# Monlock5x7_buffered.net
KiCad netlist of a schematic drawn in EAGLE
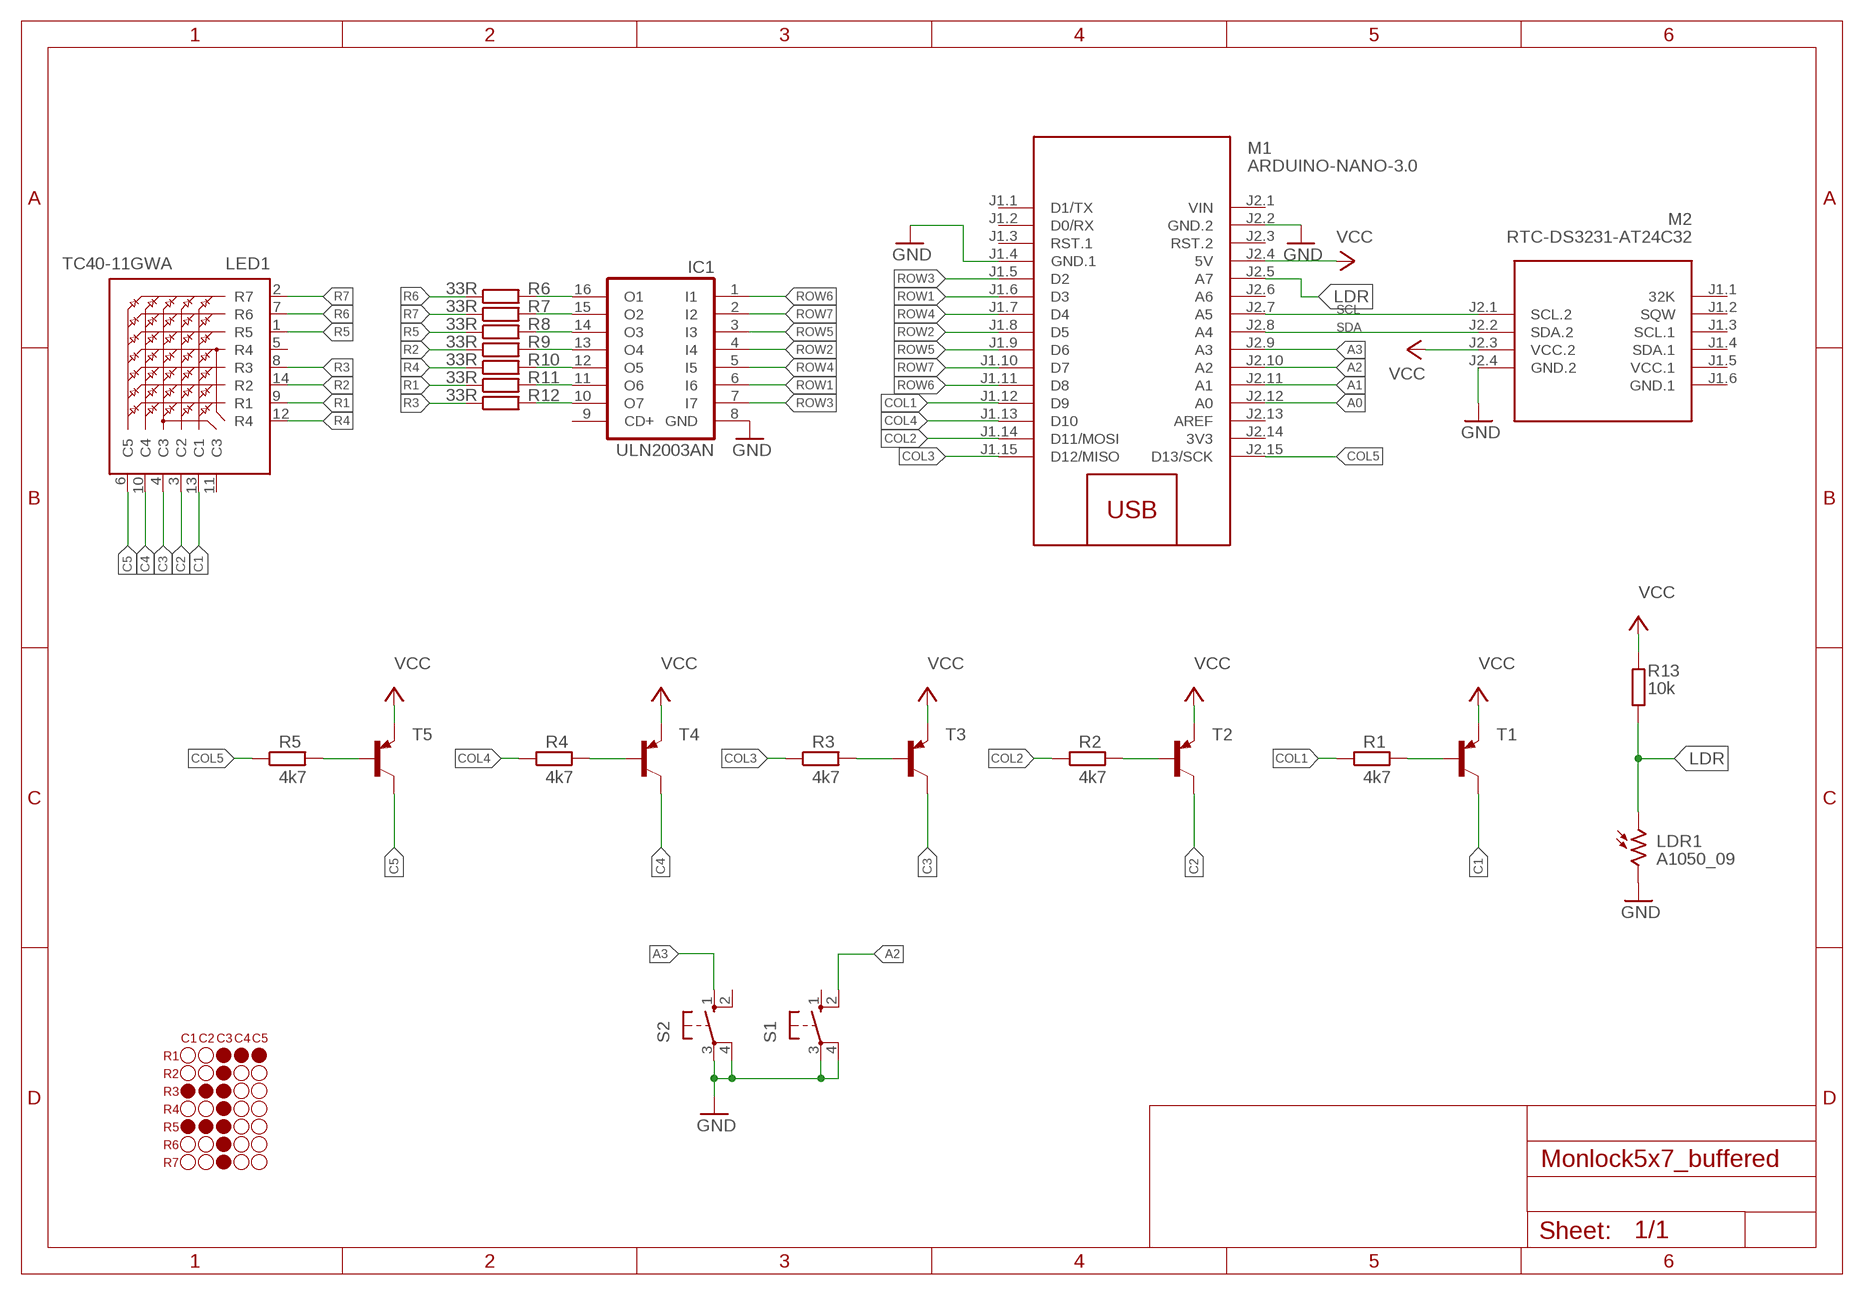
[diagram p0: schematic, sheet 1]

(export (version "E")
  (design (tool "Eeschema 10.0.6"))
  (components
    (comp (ref "IC1")
      (value "ULN2003AN")
      (footprint "eagle-import:DIL16")
      (libsource (lib "eagle-import") (part "ULN2003AN"))
    )
    (comp (ref "LDR1")
      (value "A1050_09")
      (footprint "eagle-import:T0-46-A10XX")
      (libsource (lib "eagle-import") (part "A1050_09"))
    )
    (comp (ref "LED1")
      (value "TC40-11GWA")
      (footprint "eagle-import:TC40-11GWA")
      (libsource (lib "eagle-import") (part "TC40-11GWA"))
    )
    (comp (ref "M1")
      (value "ARDUINO-NANO-3.0")
      (footprint "eagle-import:ARDUINO-NANO-3.0")
      (libsource (lib "eagle-import") (part "ARDUINO-NANO-3.0"))
    )
    (comp (ref "M2")
      (value "RTC-DS3231-AT24C32")
      (footprint "eagle-import:RTC-DS3231-AT24C32")
      (libsource (lib "eagle-import") (part "RTC-DS3231-AT24C32"))
    )
    (comp (ref "R1")
      (value "4k7")
      (footprint "eagle-import:0204_7")
      (libsource (lib "eagle-import") (part "R-EU_0204/7"))
    )
    (comp (ref "R2")
      (value "4k7")
      (footprint "eagle-import:0204_7")
      (libsource (lib "eagle-import") (part "R-EU_0204/7"))
    )
    (comp (ref "R3")
      (value "4k7")
      (footprint "eagle-import:0204_7")
      (libsource (lib "eagle-import") (part "R-EU_0204/7"))
    )
    (comp (ref "R4")
      (value "4k7")
      (footprint "eagle-import:0204_7")
      (libsource (lib "eagle-import") (part "R-EU_0204/7"))
    )
    (comp (ref "R5")
      (value "4k7")
      (footprint "eagle-import:0204_7")
      (libsource (lib "eagle-import") (part "R-EU_0204/7"))
    )
    (comp (ref "R6")
      (value "33R")
      (footprint "eagle-import:0204_7")
      (libsource (lib "eagle-import") (part "R-EU_0204/7"))
    )
    (comp (ref "R7")
      (value "33R")
      (footprint "eagle-import:0204_7")
      (libsource (lib "eagle-import") (part "R-EU_0204/7"))
    )
    (comp (ref "R8")
      (value "33R")
      (footprint "eagle-import:0204_7")
      (libsource (lib "eagle-import") (part "R-EU_0204/7"))
    )
    (comp (ref "R9")
      (value "33R")
      (footprint "eagle-import:0204_7")
      (libsource (lib "eagle-import") (part "R-EU_0204/7"))
    )
    (comp (ref "R10")
      (value "33R")
      (footprint "eagle-import:0204_7")
      (libsource (lib "eagle-import") (part "R-EU_0204/7"))
    )
    (comp (ref "R11")
      (value "33R")
      (footprint "eagle-import:0204_7")
      (libsource (lib "eagle-import") (part "R-EU_0204/7"))
    )
    (comp (ref "R12")
      (value "33R")
      (footprint "eagle-import:0204_7")
      (libsource (lib "eagle-import") (part "R-EU_0204/7"))
    )
    (comp (ref "R13")
      (value "10k")
      (footprint "eagle-import:0204_7")
      (libsource (lib "eagle-import") (part "R-EU_0204/7"))
    )
    (comp (ref "S1")
      (value "40-XX")
      (footprint "eagle-import:B3F-40XX")
      (fields (field (name "MF") "OMRON COMPONENTS USA") (field (name "MPN") "B3F-4000"))
      (libsource (lib "eagle-import") (part "40-XX"))
    )
    (comp (ref "S2")
      (value "40-XX")
      (footprint "eagle-import:B3F-40XX")
      (fields (field (name "MF") "OMRON COMPONENTS USA") (field (name "MPN") "B3F-4000"))
      (libsource (lib "eagle-import") (part "40-XX"))
    )
    (comp (ref "T1")
      (value "BC327-PNP-TO92-EBC")
      (footprint "eagle-import:TO92-EBC")
      (libsource (lib "eagle-import") (part "-PNP-TO92-EBCBC327"))
    )
    (comp (ref "T2")
      (value "BC327-PNP-TO92-EBC")
      (footprint "eagle-import:TO92-EBC")
      (libsource (lib "eagle-import") (part "-PNP-TO92-EBCBC327"))
    )
    (comp (ref "T3")
      (value "BC327-PNP-TO92-EBC")
      (footprint "eagle-import:TO92-EBC")
      (libsource (lib "eagle-import") (part "-PNP-TO92-EBCBC327"))
    )
    (comp (ref "T4")
      (value "BC327-PNP-TO92-EBC")
      (footprint "eagle-import:TO92-EBC")
      (libsource (lib "eagle-import") (part "-PNP-TO92-EBCBC327"))
    )
    (comp (ref "T5")
      (value "BC327-PNP-TO92-EBC")
      (footprint "eagle-import:TO92-EBC")
      (libsource (lib "eagle-import") (part "-PNP-TO92-EBCBC327"))
    )
  )
  (nets
    (net (code "1") (name "/3V3") (class "Default")
      (node (ref "M1") (pin "J2.14") (pinfunction "3V3_J2.14") (pintype "power_in"))
    )
    (net (code "2") (name "/GND.1") (class "Default")
      (node (ref "M2") (pin "J1.6") (pinfunction "GND.1_J1.6") (pintype "power_in"))
    )
    (net (code "3") (name "/SCL") (class "Default")
      (node (ref "M1") (pin "J2.7") (pinfunction "A5_J2.7") (pintype "bidirectional"))
      (node (ref "M2") (pin "J2.1") (pinfunction "SCL.2_J2.1") (pintype "bidirectional"))
    )
    (net (code "4") (name "/SDA") (class "Default")
      (node (ref "M1") (pin "J2.8") (pinfunction "A4_J2.8") (pintype "bidirectional"))
      (node (ref "M2") (pin "J2.2") (pinfunction "SDA.2_J2.2") (pintype "bidirectional"))
    )
    (net (code "5") (name "/VCC.1") (class "Default")
      (node (ref "M2") (pin "J1.5") (pinfunction "VCC.1_J1.5") (pintype "power_in"))
    )
    (net (code "6") (name "/VIN") (class "Default")
      (node (ref "M1") (pin "J2.1") (pinfunction "VIN_J2.1") (pintype "power_in"))
    )
    (net (code "7") (name "A0") (class "Default")
      (node (ref "M1") (pin "J2.12") (pinfunction "A0_J2.12") (pintype "bidirectional"))
    )
    (net (code "8") (name "A1") (class "Default")
      (node (ref "M1") (pin "J2.11") (pinfunction "A1_J2.11") (pintype "bidirectional"))
    )
    (net (code "9") (name "A2") (class "Default")
      (node (ref "M1") (pin "J2.10") (pinfunction "A2_J2.10") (pintype "bidirectional"))
      (node (ref "S1") (pin "2") (pinfunction "S1_2") (pintype "passive"))
    )
    (net (code "10") (name "A3") (class "Default")
      (node (ref "M1") (pin "J2.9") (pinfunction "A3_J2.9") (pintype "bidirectional"))
      (node (ref "S2") (pin "1") (pinfunction "S_1") (pintype "passive"))
    )
    (net (code "11") (name "C1") (class "Default")
      (node (ref "LED1") (pin "13") (pinfunction "C1_13") (pintype "passive"))
      (node (ref "T1") (pin "C") (pinfunction "C_C") (pintype "passive"))
    )
    (net (code "12") (name "C2") (class "Default")
      (node (ref "LED1") (pin "3") (pinfunction "C2_3") (pintype "passive"))
      (node (ref "T2") (pin "C") (pinfunction "C_C") (pintype "passive"))
    )
    (net (code "13") (name "C3") (class "Default")
      (node (ref "LED1") (pin "4") (pinfunction "C3_4") (pintype "passive"))
      (node (ref "T3") (pin "C") (pinfunction "C_C") (pintype "passive"))
    )
    (net (code "14") (name "C4") (class "Default")
      (node (ref "LED1") (pin "10") (pinfunction "C4_10") (pintype "passive"))
      (node (ref "T4") (pin "C") (pinfunction "C_C") (pintype "passive"))
    )
    (net (code "15") (name "C5") (class "Default")
      (node (ref "LED1") (pin "6") (pinfunction "C5_6") (pintype "passive"))
      (node (ref "T5") (pin "C") (pinfunction "C_C") (pintype "passive"))
    )
    (net (code "16") (name "COL1") (class "Default")
      (node (ref "M1") (pin "J1.12") (pinfunction "D9_J1.12") (pintype "bidirectional"))
      (node (ref "R1") (pin "1") (pinfunction "1_1") (pintype "passive"))
    )
    (net (code "17") (name "COL2") (class "Default")
      (node (ref "M1") (pin "J1.14") (pinfunction "D11/MOSI_J1.14") (pintype "bidirectional"))
      (node (ref "R2") (pin "1") (pinfunction "1_1") (pintype "passive"))
    )
    (net (code "18") (name "COL3") (class "Default")
      (node (ref "M1") (pin "J1.15") (pinfunction "D12/MISO_J1.15") (pintype "bidirectional"))
      (node (ref "R3") (pin "1") (pinfunction "1_1") (pintype "passive"))
    )
    (net (code "19") (name "COL4") (class "Default")
      (node (ref "M1") (pin "J1.13") (pinfunction "D10_J1.13") (pintype "bidirectional"))
      (node (ref "R4") (pin "1") (pinfunction "1_1") (pintype "passive"))
    )
    (net (code "20") (name "COL5") (class "Default")
      (node (ref "M1") (pin "J2.15") (pinfunction "D13/SCK_J2.15") (pintype "bidirectional"))
      (node (ref "R5") (pin "1") (pinfunction "1_1") (pintype "passive"))
    )
    (net (code "21") (name "GND") (class "Default")
      (node (ref "IC1") (pin "8") (pinfunction "GND_8") (pintype "power_in"))
      (node (ref "LDR1") (pin "2") (pinfunction "2_2") (pintype "passive"))
      (node (ref "M1") (pin "J1.4") (pinfunction "GND.1_J1.4") (pintype "power_in"))
      (node (ref "M1") (pin "J2.2") (pinfunction "GND.2_J2.2") (pintype "power_in"))
      (node (ref "M2") (pin "J2.4") (pinfunction "GND.2_J2.4") (pintype "power_in"))
      (node (ref "S1") (pin "3") (pinfunction "P_3") (pintype "passive"))
      (node (ref "S1") (pin "4") (pinfunction "P1_4") (pintype "passive"))
      (node (ref "S2") (pin "3") (pinfunction "P_3") (pintype "passive"))
      (node (ref "S2") (pin "4") (pinfunction "P1_4") (pintype "passive"))
    )
    (net (code "22") (name "LDR") (class "Default")
      (node (ref "LDR1") (pin "1") (pinfunction "1_1") (pintype "passive"))
      (node (ref "M1") (pin "J2.5") (pinfunction "A7_J2.5") (pintype "bidirectional"))
      (node (ref "R13") (pin "1") (pinfunction "1_1") (pintype "passive"))
    )
    (net (code "23") (name "Net-(IC1-O1)") (class "Default")
      (node (ref "IC1") (pin "16") (pinfunction "O1_16") (pintype "open_collector"))
      (node (ref "R6") (pin "2") (pinfunction "2_2") (pintype "passive"))
    )
    (net (code "24") (name "Net-(IC1-O2)") (class "Default")
      (node (ref "IC1") (pin "15") (pinfunction "O2_15") (pintype "open_collector"))
      (node (ref "R7") (pin "2") (pinfunction "2_2") (pintype "passive"))
    )
    (net (code "25") (name "Net-(IC1-O3)") (class "Default")
      (node (ref "IC1") (pin "14") (pinfunction "O3_14") (pintype "open_collector"))
      (node (ref "R8") (pin "2") (pinfunction "2_2") (pintype "passive"))
    )
    (net (code "26") (name "Net-(IC1-O4)") (class "Default")
      (node (ref "IC1") (pin "13") (pinfunction "O4_13") (pintype "open_collector"))
      (node (ref "R9") (pin "2") (pinfunction "2_2") (pintype "passive"))
    )
    (net (code "27") (name "Net-(IC1-O5)") (class "Default")
      (node (ref "IC1") (pin "12") (pinfunction "O5_12") (pintype "open_collector"))
      (node (ref "R10") (pin "2") (pinfunction "2_2") (pintype "passive"))
    )
    (net (code "28") (name "Net-(IC1-O6)") (class "Default")
      (node (ref "IC1") (pin "11") (pinfunction "O6_11") (pintype "open_collector"))
      (node (ref "R11") (pin "2") (pinfunction "2_2") (pintype "passive"))
    )
    (net (code "29") (name "Net-(IC1-O7)") (class "Default")
      (node (ref "IC1") (pin "10") (pinfunction "O7_10") (pintype "open_collector"))
      (node (ref "R12") (pin "2") (pinfunction "2_2") (pintype "passive"))
    )
    (net (code "30") (name "Net-(R1-Pad2)") (class "Default")
      (node (ref "R1") (pin "2") (pinfunction "2_2") (pintype "passive"))
      (node (ref "T1") (pin "B") (pinfunction "B_B") (pintype "passive"))
    )
    (net (code "31") (name "Net-(R2-Pad2)") (class "Default")
      (node (ref "R2") (pin "2") (pinfunction "2_2") (pintype "passive"))
      (node (ref "T2") (pin "B") (pinfunction "B_B") (pintype "passive"))
    )
    (net (code "32") (name "Net-(R3-Pad2)") (class "Default")
      (node (ref "R3") (pin "2") (pinfunction "2_2") (pintype "passive"))
      (node (ref "T3") (pin "B") (pinfunction "B_B") (pintype "passive"))
    )
    (net (code "33") (name "Net-(R4-Pad2)") (class "Default")
      (node (ref "R4") (pin "2") (pinfunction "2_2") (pintype "passive"))
      (node (ref "T4") (pin "B") (pinfunction "B_B") (pintype "passive"))
    )
    (net (code "34") (name "Net-(R5-Pad2)") (class "Default")
      (node (ref "R5") (pin "2") (pinfunction "2_2") (pintype "passive"))
      (node (ref "T5") (pin "B") (pinfunction "B_B") (pintype "passive"))
    )
    (net (code "35") (name "R1") (class "Default")
      (node (ref "LED1") (pin "9") (pinfunction "R1_9") (pintype "passive"))
      (node (ref "R11") (pin "1") (pinfunction "1_1") (pintype "passive"))
    )
    (net (code "36") (name "R2") (class "Default")
      (node (ref "LED1") (pin "14") (pinfunction "R2_14") (pintype "passive"))
      (node (ref "R9") (pin "1") (pinfunction "1_1") (pintype "passive"))
    )
    (net (code "37") (name "R3") (class "Default")
      (node (ref "LED1") (pin "8") (pinfunction "R3_8") (pintype "passive"))
      (node (ref "R12") (pin "1") (pinfunction "1_1") (pintype "passive"))
    )
    (net (code "38") (name "R4") (class "Default")
      (node (ref "LED1") (pin "12") (pinfunction "R4_12") (pintype "passive"))
      (node (ref "R10") (pin "1") (pinfunction "1_1") (pintype "passive"))
    )
    (net (code "39") (name "R5") (class "Default")
      (node (ref "LED1") (pin "1") (pinfunction "R5_1") (pintype "passive"))
      (node (ref "R8") (pin "1") (pinfunction "1_1") (pintype "passive"))
    )
    (net (code "40") (name "R6") (class "Default")
      (node (ref "LED1") (pin "7") (pinfunction "R6_7") (pintype "passive"))
      (node (ref "R6") (pin "1") (pinfunction "1_1") (pintype "passive"))
    )
    (net (code "41") (name "R7") (class "Default")
      (node (ref "LED1") (pin "2") (pinfunction "R7_2") (pintype "passive"))
      (node (ref "R7") (pin "1") (pinfunction "1_1") (pintype "passive"))
    )
    (net (code "42") (name "ROW1") (class "Default")
      (node (ref "IC1") (pin "6") (pinfunction "I6_6") (pintype "input"))
      (node (ref "M1") (pin "J1.6") (pinfunction "D3_J1.6") (pintype "bidirectional"))
    )
    (net (code "43") (name "ROW2") (class "Default")
      (node (ref "IC1") (pin "4") (pinfunction "I4_4") (pintype "input"))
      (node (ref "M1") (pin "J1.8") (pinfunction "D5_J1.8") (pintype "bidirectional"))
    )
    (net (code "44") (name "ROW3") (class "Default")
      (node (ref "IC1") (pin "7") (pinfunction "I7_7") (pintype "input"))
      (node (ref "M1") (pin "J1.5") (pinfunction "D2_J1.5") (pintype "bidirectional"))
    )
    (net (code "45") (name "ROW4") (class "Default")
      (node (ref "IC1") (pin "5") (pinfunction "I5_5") (pintype "input"))
      (node (ref "M1") (pin "J1.7") (pinfunction "D4_J1.7") (pintype "bidirectional"))
    )
    (net (code "46") (name "ROW5") (class "Default")
      (node (ref "IC1") (pin "3") (pinfunction "I3_3") (pintype "input"))
      (node (ref "M1") (pin "J1.9") (pinfunction "D6_J1.9") (pintype "bidirectional"))
    )
    (net (code "47") (name "ROW6") (class "Default")
      (node (ref "IC1") (pin "1") (pinfunction "I1_1") (pintype "input"))
      (node (ref "M1") (pin "J1.11") (pinfunction "D8_J1.11") (pintype "bidirectional"))
    )
    (net (code "48") (name "ROW7") (class "Default")
      (node (ref "IC1") (pin "2") (pinfunction "I2_2") (pintype "input"))
      (node (ref "M1") (pin "J1.10") (pinfunction "D7_J1.10") (pintype "bidirectional"))
    )
    (net (code "49") (name "VCC") (class "Default")
      (node (ref "M1") (pin "J2.4") (pinfunction "5V_J2.4") (pintype "power_in"))
      (node (ref "M2") (pin "J2.3") (pinfunction "VCC.2_J2.3") (pintype "power_in"))
      (node (ref "R13") (pin "2") (pinfunction "2_2") (pintype "passive"))
      (node (ref "T1") (pin "E") (pinfunction "E_E") (pintype "passive"))
      (node (ref "T2") (pin "E") (pinfunction "E_E") (pintype "passive"))
      (node (ref "T3") (pin "E") (pinfunction "E_E") (pintype "passive"))
      (node (ref "T4") (pin "E") (pinfunction "E_E") (pintype "passive"))
      (node (ref "T5") (pin "E") (pinfunction "E_E") (pintype "passive"))
    )
    (net (code "50") (name "unconnected-(IC1-CD+-Pad9)") (class "Default")
      (node (ref "IC1") (pin "9") (pinfunction "CD+_9") (pintype "passive"))
    )
    (net (code "51") (name "unconnected-(LED1-C3-Pad11)") (class "Default")
      (node (ref "LED1") (pin "11") (pinfunction "C3_11") (pintype "passive"))
    )
    (net (code "52") (name "unconnected-(LED1-R4-Pad5)") (class "Default")
      (node (ref "LED1") (pin "5") (pinfunction "R4_5") (pintype "passive"))
    )
    (net (code "53") (name "unconnected-(M1-A6-PadJ2.6)") (class "Default")
      (node (ref "M1") (pin "J2.6") (pinfunction "A6_J2.6") (pintype "bidirectional"))
    )
    (net (code "54") (name "unconnected-(M1-AREF-PadJ2.13)") (class "Default")
      (node (ref "M1") (pin "J2.13") (pinfunction "AREF_J2.13") (pintype "bidirectional"))
    )
    (net (code "55") (name "unconnected-(M1-D0{slash}RX-PadJ1.2)") (class "Default")
      (node (ref "M1") (pin "J1.2") (pinfunction "D0/RX_J1.2") (pintype "bidirectional"))
    )
    (net (code "56") (name "unconnected-(M1-D1{slash}TX-PadJ1.1)") (class "Default")
      (node (ref "M1") (pin "J1.1") (pinfunction "D1/TX_J1.1") (pintype "bidirectional"))
    )
    (net (code "57") (name "unconnected-(M1-RST.1-PadJ1.3)") (class "Default")
      (node (ref "M1") (pin "J1.3") (pinfunction "RST.1_J1.3") (pintype "bidirectional"))
    )
    (net (code "58") (name "unconnected-(M1-RST.2-PadJ2.3)") (class "Default")
      (node (ref "M1") (pin "J2.3") (pinfunction "RST.2_J2.3") (pintype "bidirectional"))
    )
    (net (code "59") (name "unconnected-(M2-32K-PadJ1.1)") (class "Default")
      (node (ref "M2") (pin "J1.1") (pinfunction "32K_J1.1") (pintype "bidirectional"))
    )
    (net (code "60") (name "unconnected-(M2-SCL.1-PadJ1.3)") (class "Default")
      (node (ref "M2") (pin "J1.3") (pinfunction "SCL.1_J1.3") (pintype "bidirectional"))
    )
    (net (code "61") (name "unconnected-(M2-SDA.1-PadJ1.4)") (class "Default")
      (node (ref "M2") (pin "J1.4") (pinfunction "SDA.1_J1.4") (pintype "bidirectional"))
    )
    (net (code "62") (name "unconnected-(M2-SQW-PadJ1.2)") (class "Default")
      (node (ref "M2") (pin "J1.2") (pinfunction "SQW_J1.2") (pintype "bidirectional"))
    )
    (net (code "63") (name "unconnected-(S1-S-Pad1)") (class "Default")
      (node (ref "S1") (pin "1") (pinfunction "S_1") (pintype "passive"))
    )
    (net (code "64") (name "unconnected-(S2-S1-Pad2)") (class "Default")
      (node (ref "S2") (pin "2") (pinfunction "S1_2") (pintype "passive"))
    )
  )
)
